# bbb.net
KiCad netlist of a schematic drawn in Altium Designer
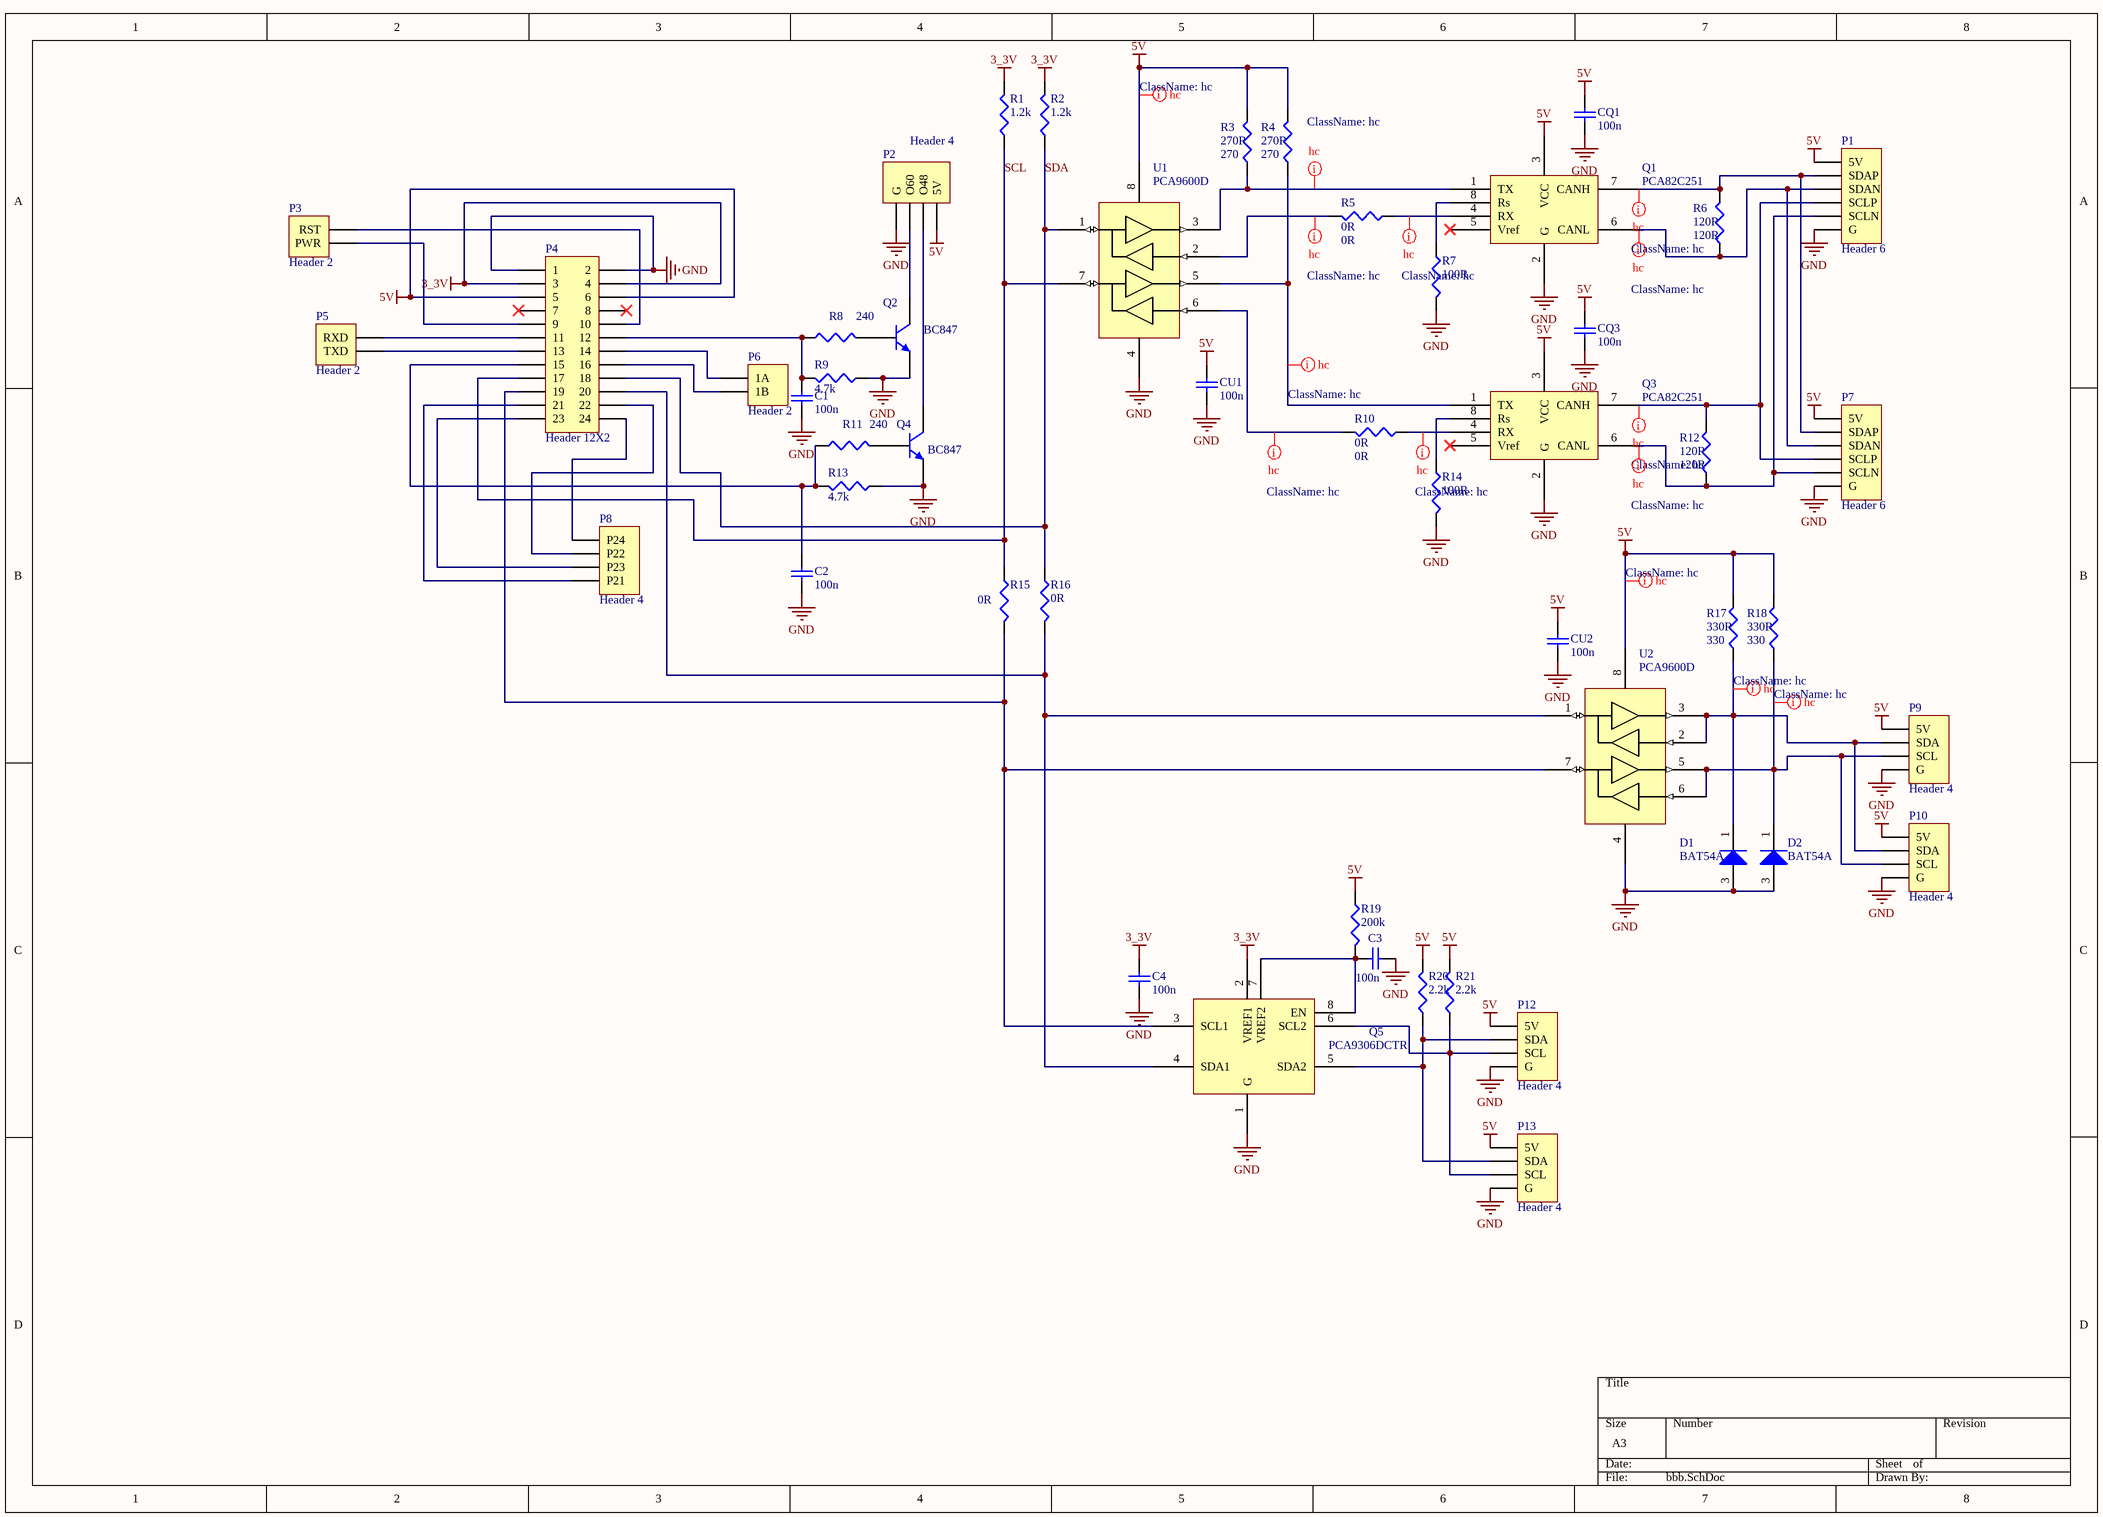
[diagram p0: bbb.SchDoc]

(export (version "E")
  (design (tool "Eeschema 10.0.6"))
  (components
    (comp (ref "C1")
      (value "100n")
      (footprint "1608[0603]")
      (description "Capacitor (Semiconductor SIM Model)")
      (fields (field (name "PUBLISHER") "Altium Limited"))
      (libsource (lib "Miscellaneous Devices") (part "Cap Semi"))
    )
    (comp (ref "C2")
      (value "100n")
      (footprint "1608[0603]")
      (description "Capacitor (Semiconductor SIM Model)")
      (fields (field (name "PUBLISHER") "Altium Limited"))
      (libsource (lib "Miscellaneous Devices") (part "Cap Semi"))
    )
    (comp (ref "C3")
      (value "100n")
      (footprint "C1206")
      (description "Capacitor (Semiconductor SIM Model)")
      (fields (field (name "PUBLISHER") "Altium Limited"))
      (libsource (lib "Miscellaneous Devices") (part "Cap Semi"))
    )
    (comp (ref "C4")
      (value "100n")
      (footprint "C1206")
      (description "Capacitor (Semiconductor SIM Model)")
      (fields (field (name "PUBLISHER") "Altium Limited"))
      (libsource (lib "Miscellaneous Devices") (part "Cap Semi"))
    )
    (comp (ref "CQ1")
      (value "100n")
      (footprint "C1206")
      (description "Capacitor (Semiconductor SIM Model)")
      (fields (field (name "PUBLISHER") "Altium Limited"))
      (libsource (lib "Miscellaneous Devices") (part "Cap Semi"))
    )
    (comp (ref "CQ3")
      (value "100n")
      (footprint "C1206")
      (description "Capacitor (Semiconductor SIM Model)")
      (fields (field (name "PUBLISHER") "Altium Limited"))
      (libsource (lib "Miscellaneous Devices") (part "Cap Semi"))
    )
    (comp (ref "CU1")
      (value "100n")
      (footprint "C1206")
      (description "Capacitor (Semiconductor SIM Model)")
      (fields (field (name "PUBLISHER") "Altium Limited"))
      (libsource (lib "Miscellaneous Devices") (part "Cap Semi"))
    )
    (comp (ref "CU2")
      (value "100n")
      (footprint "C1206")
      (description "Capacitor (Semiconductor SIM Model)")
      (fields (field (name "PUBLISHER") "Altium Limited"))
      (libsource (lib "Miscellaneous Devices") (part "Cap Semi"))
    )
    (comp (ref "D1")
      (value "BAT54A")
      (footprint "SOT-23_N")
      (description "Default Diode")
      (fields (field (name "PUBLISHER") "Altium Limited"))
      (libsource (lib "Miscellaneous Devices") (part "Diode"))
    )
    (comp (ref "D2")
      (value "BAT54A")
      (footprint "SOT-23_N")
      (description "Default Diode")
      (fields (field (name "PUBLISHER") "Altium Limited"))
      (libsource (lib "Miscellaneous Devices") (part "Diode"))
    )
    (comp (ref "P1")
      (value "Header 6")
      (footprint "HDR1X6")
      (description "Header, 6-Pin")
      (fields (field (name "PUBLISHER") "Altium Limited"))
      (libsource (lib "Miscellaneous Connectors") (part "Header 6"))
    )
    (comp (ref "P2")
      (value "Header 4")
      (footprint "HDR1X4")
      (description "Header, 4-Pin")
      (fields (field (name "PUBLISHER") "Altium Limited"))
      (libsource (lib "Miscellaneous Connectors") (part "Header 4"))
    )
    (comp (ref "P3")
      (value "Header 2")
      (footprint "HDR1X2")
      (description "Header, 2-Pin")
      (fields (field (name "PUBLISHER") "Altium Limited"))
      (libsource (lib "Miscellaneous Connectors") (part "Header 2"))
    )
    (comp (ref "P4")
      (value "Header 12X2")
      (footprint "HDR2X12")
      (description "Header, 12-Pin, Dual row")
      (fields (field (name "PUBLISHER") "Altium Limited"))
      (libsource (lib "Miscellaneous Connectors") (part "Header 12X2"))
    )
    (comp (ref "P5")
      (value "Header 2")
      (footprint "HDR1X2")
      (description "Header, 2-Pin")
      (fields (field (name "PUBLISHER") "Altium Limited"))
      (libsource (lib "Miscellaneous Connectors") (part "Header 2"))
    )
    (comp (ref "P6")
      (value "Header 2")
      (footprint "HDR1X2")
      (description "Header, 2-Pin")
      (fields (field (name "PUBLISHER") "Altium Limited"))
      (libsource (lib "") (part "Header 2_1"))
    )
    (comp (ref "P7")
      (value "Header 6")
      (footprint "HDR1X6")
      (description "Header, 6-Pin")
      (fields (field (name "PUBLISHER") "Altium Limited"))
      (libsource (lib "Miscellaneous Connectors") (part "Header 6"))
    )
    (comp (ref "P8")
      (value "Header 4")
      (footprint "HDR1X4")
      (description "Header, 4-Pin")
      (fields (field (name "PUBLISHER") "Altium Limited"))
      (libsource (lib "Miscellaneous Connectors") (part "Header 4"))
    )
    (comp (ref "P9")
      (value "Header 4")
      (footprint "HDR1X4")
      (description "Header, 4-Pin")
      (fields (field (name "PUBLISHER") "Altium Limited"))
      (libsource (lib "Miscellaneous Connectors") (part "Header 4"))
    )
    (comp (ref "P10")
      (value "Header 4")
      (footprint "HDR1X4")
      (description "Header, 4-Pin")
      (fields (field (name "PUBLISHER") "Altium Limited"))
      (libsource (lib "Miscellaneous Connectors") (part "Header 4"))
    )
    (comp (ref "P12")
      (value "Header 4")
      (footprint "HDR1X4")
      (description "Header, 4-Pin")
      (fields (field (name "PUBLISHER") "Altium Limited"))
      (libsource (lib "Miscellaneous Connectors") (part "Header 4"))
    )
    (comp (ref "P13")
      (value "Header 4")
      (footprint "HDR1X4")
      (description "Header, 4-Pin")
      (fields (field (name "PUBLISHER") "Altium Limited"))
      (libsource (lib "Miscellaneous Connectors") (part "Header 4"))
    )
    (comp (ref "Q1") (value "PCA82C251") (footprint "SOIC150-8_M") (libsource (lib "PCA") (part "PCA82C251")))
    (comp (ref "Q2")
      (value "BC847")
      (footprint "SOT-23B_N")
      (description "NPN Bipolar Transistor")
      (fields (field (name "PUBLISHER") "Altium Limited"))
      (libsource (lib "Miscellaneous Devices") (part "QNPN"))
    )
    (comp (ref "Q3") (value "PCA82C251") (footprint "SOIC150-8_M") (libsource (lib "PCA") (part "PCA82C251")))
    (comp (ref "Q4")
      (value "BC847")
      (footprint "SOT-23B_N")
      (description "NPN Bipolar Transistor")
      (fields (field (name "PUBLISHER") "Altium Limited"))
      (libsource (lib "Miscellaneous Devices") (part "QNPN"))
    )
    (comp (ref "Q5")
      (value "PCA9306DCTR")
      (footprint "DCT")
      (description "PCA9306")
      (libsource (lib "PCA") (part "PCA9306"))
    )
    (comp (ref "R1")
      (value "1.2k")
      (footprint "J1-0603")
      (description "Resistor")
      (fields (field (name "PUBLISHER") "Altium Limited"))
      (libsource (lib "Miscellaneous Devices") (part "Res3"))
    )
    (comp (ref "R2")
      (value "1.2k")
      (footprint "J1-0603")
      (description "Resistor")
      (fields (field (name "PUBLISHER") "Altium Limited"))
      (libsource (lib "Miscellaneous Devices") (part "Res3"))
    )
    (comp (ref "R3")
      (value "270R")
      (footprint "R1206")
      (description "Resistor")
      (fields (field (name "ALTIUM_VALUE") "270") (field (name "PUBLISHER") "Altium Limited"))
      (libsource (lib "Miscellaneous Devices") (part "Res3"))
    )
    (comp (ref "R4")
      (value "270R")
      (footprint "R1206")
      (description "Resistor")
      (fields (field (name "ALTIUM_VALUE") "270") (field (name "PUBLISHER") "Altium Limited"))
      (libsource (lib "Miscellaneous Devices") (part "Res3"))
    )
    (comp (ref "R5")
      (value "0R")
      (footprint "R1206")
      (description "Resistor")
      (fields (field (name "ALTIUM_VALUE") "0R") (field (name "PUBLISHER") "Altium Limited"))
      (libsource (lib "Miscellaneous Devices") (part "Res3"))
    )
    (comp (ref "R6")
      (value "120R")
      (footprint "R1206")
      (description "Resistor")
      (fields (field (name "ALTIUM_VALUE") "120R") (field (name "PUBLISHER") "Altium Limited"))
      (libsource (lib "Miscellaneous Devices") (part "Res3"))
    )
    (comp (ref "R7")
      (value "100R")
      (footprint "J1-0603")
      (description "Resistor")
      (fields (field (name "PUBLISHER") "Altium Limited"))
      (libsource (lib "Miscellaneous Devices") (part "Res3"))
    )
    (comp (ref "R8")
      (value "240")
      (footprint "J1-0603")
      (description "Resistor")
      (fields (field (name "Comment") "240R") (field (name "PUBLISHER") "Altium Limited"))
      (libsource (lib "Miscellaneous Devices") (part "Res3"))
    )
    (comp (ref "R9")
      (value "4.7k")
      (footprint "J1-0603")
      (description "Resistor")
      (fields (field (name "PUBLISHER") "Altium Limited"))
      (libsource (lib "Miscellaneous Devices") (part "Res3"))
    )
    (comp (ref "R10")
      (value "0R")
      (footprint "R1206")
      (description "Resistor")
      (fields (field (name "ALTIUM_VALUE") "0R") (field (name "PUBLISHER") "Altium Limited"))
      (libsource (lib "Miscellaneous Devices") (part "Res3"))
    )
    (comp (ref "R11")
      (value "240")
      (footprint "J1-0603")
      (description "Resistor")
      (fields (field (name "Comment") "240R") (field (name "PUBLISHER") "Altium Limited"))
      (libsource (lib "Miscellaneous Devices") (part "Res3"))
    )
    (comp (ref "R12")
      (value "120R")
      (footprint "R1206")
      (description "Resistor")
      (fields (field (name "ALTIUM_VALUE") "120R") (field (name "PUBLISHER") "Altium Limited"))
      (libsource (lib "Miscellaneous Devices") (part "Res3"))
    )
    (comp (ref "R13")
      (value "4.7k")
      (footprint "J1-0603")
      (description "Resistor")
      (fields (field (name "PUBLISHER") "Altium Limited"))
      (libsource (lib "Miscellaneous Devices") (part "Res3"))
    )
    (comp (ref "R14")
      (value "100R")
      (footprint "J1-0603")
      (description "Resistor")
      (fields (field (name "PUBLISHER") "Altium Limited"))
      (libsource (lib "Miscellaneous Devices") (part "Res3"))
    )
    (comp (ref "R15")
      (value "0R")
      (footprint "J1-0603")
      (description "Resistor")
      (fields (field (name "PUBLISHER") "Altium Limited"))
      (libsource (lib "Miscellaneous Devices") (part "Res3"))
    )
    (comp (ref "R16")
      (value "0R")
      (footprint "J1-0603")
      (description "Resistor")
      (fields (field (name "PUBLISHER") "Altium Limited"))
      (libsource (lib "Miscellaneous Devices") (part "Res3"))
    )
    (comp (ref "R17")
      (value "330R")
      (footprint "R1206")
      (description "Resistor")
      (fields (field (name "ALTIUM_VALUE") "330") (field (name "PUBLISHER") "Altium Limited"))
      (libsource (lib "Miscellaneous Devices") (part "Res3"))
    )
    (comp (ref "R18")
      (value "330R")
      (footprint "R1206")
      (description "Resistor")
      (fields (field (name "ALTIUM_VALUE") "330") (field (name "PUBLISHER") "Altium Limited"))
      (libsource (lib "Miscellaneous Devices") (part "Res3"))
    )
    (comp (ref "R19")
      (value "200k")
      (footprint "J1-0603")
      (description "Resistor")
      (fields (field (name "PUBLISHER") "Altium Limited"))
      (libsource (lib "Miscellaneous Devices") (part "Res3"))
    )
    (comp (ref "R20")
      (value "2.2k")
      (footprint "J1-0603")
      (description "Resistor")
      (fields (field (name "PUBLISHER") "Altium Limited"))
      (libsource (lib "Miscellaneous Devices") (part "Res3"))
    )
    (comp (ref "R21")
      (value "2.2k")
      (footprint "J1-0603")
      (description "Resistor")
      (fields (field (name "PUBLISHER") "Altium Limited"))
      (libsource (lib "Miscellaneous Devices") (part "Res3"))
    )
    (comp (ref "U1") (value "PCA9600D") (footprint "SOIC150-8_M") (libsource (lib "misc") (part "P82B96")))
    (comp (ref "U2") (value "PCA9600D") (footprint "SOIC150-8_M") (libsource (lib "misc") (part "P82B96")))
  )
  (nets
    (net (code "1") (name "/SCL") (class "Default")
      (node (ref "P4") (pin "17") (pinfunction "17_17") (pintype "passive"))
      (node (ref "R1") (pin "1") (pinfunction "1_1") (pintype "passive"))
      (node (ref "R15") (pin "1") (pinfunction "1_1") (pintype "passive"))
      (node (ref "U1") (pin "7") (pinfunction "7_7") (pintype "bidirectional"))
    )
    (net (code "2") (name "/SDA") (class "Default")
      (node (ref "P4") (pin "18") (pinfunction "18_18") (pintype "passive"))
      (node (ref "R16") (pin "1") (pinfunction "1_1") (pintype "passive"))
      (node (ref "R2") (pin "1") (pinfunction "1_1") (pintype "passive"))
      (node (ref "U1") (pin "1") (pinfunction "1_1") (pintype "bidirectional"))
    )
    (net (code "3") (name "3_3V") (class "Default")
      (node (ref "C4") (pin "2") (pinfunction "2_2") (pintype "passive"))
      (node (ref "P4") (pin "3") (pinfunction "3_3") (pintype "passive"))
      (node (ref "P4") (pin "4") (pinfunction "4_4") (pintype "passive"))
      (node (ref "Q5") (pin "2") (pinfunction "VREF1_2") (pintype "passive"))
      (node (ref "R1") (pin "2") (pinfunction "2_2") (pintype "passive"))
      (node (ref "R2") (pin "2") (pinfunction "2_2") (pintype "passive"))
    )
    (net (code "4") (name "5V") (class "Default")
      (node (ref "CQ1") (pin "2") (pinfunction "2_2") (pintype "passive"))
      (node (ref "CQ3") (pin "2") (pinfunction "2_2") (pintype "passive"))
      (node (ref "CU1") (pin "2") (pinfunction "2_2") (pintype "passive"))
      (node (ref "CU2") (pin "2") (pinfunction "2_2") (pintype "passive"))
      (node (ref "P1") (pin "6") (pinfunction "5V_6") (pintype "passive"))
      (node (ref "P10") (pin "4") (pinfunction "P24_4") (pintype "passive"))
      (node (ref "P12") (pin "4") (pinfunction "P24_4") (pintype "passive"))
      (node (ref "P13") (pin "4") (pinfunction "P24_4") (pintype "passive"))
      (node (ref "P2") (pin "4") (pinfunction "P24_4") (pintype "passive"))
      (node (ref "P4") (pin "5") (pinfunction "5_5") (pintype "passive"))
      (node (ref "P4") (pin "6") (pinfunction "6_6") (pintype "passive"))
      (node (ref "P7") (pin "6") (pinfunction "5V_6") (pintype "passive"))
      (node (ref "P9") (pin "4") (pinfunction "P24_4") (pintype "passive"))
      (node (ref "Q1") (pin "3") (pinfunction "VCC_3") (pintype "passive"))
      (node (ref "Q3") (pin "3") (pinfunction "VCC_3") (pintype "passive"))
      (node (ref "R17") (pin "2") (pinfunction "2_2") (pintype "passive"))
      (node (ref "R18") (pin "2") (pinfunction "2_2") (pintype "passive"))
      (node (ref "R19") (pin "1") (pinfunction "1_1") (pintype "passive"))
      (node (ref "R20") (pin "2") (pinfunction "2_2") (pintype "passive"))
      (node (ref "R21") (pin "2") (pinfunction "2_2") (pintype "passive"))
      (node (ref "R3") (pin "2") (pinfunction "2_2") (pintype "passive"))
      (node (ref "R4") (pin "2") (pinfunction "2_2") (pintype "passive"))
      (node (ref "U1") (pin "8") (pinfunction "8_8") (pintype "passive"))
      (node (ref "U2") (pin "8") (pinfunction "8_8") (pintype "passive"))
    )
    (net (code "5") (name "GND") (class "Default")
      (node (ref "C1") (pin "2") (pinfunction "2_2") (pintype "passive"))
      (node (ref "C2") (pin "2") (pinfunction "2_2") (pintype "passive"))
      (node (ref "C3") (pin "2") (pinfunction "2_2") (pintype "passive"))
      (node (ref "C4") (pin "1") (pinfunction "1_1") (pintype "passive"))
      (node (ref "CQ1") (pin "1") (pinfunction "1_1") (pintype "passive"))
      (node (ref "CQ3") (pin "1") (pinfunction "1_1") (pintype "passive"))
      (node (ref "CU1") (pin "1") (pinfunction "1_1") (pintype "passive"))
      (node (ref "CU2") (pin "1") (pinfunction "1_1") (pintype "passive"))
      (node (ref "D1") (pin "3") (pinfunction "A_3") (pintype "passive"))
      (node (ref "D2") (pin "3") (pinfunction "A_3") (pintype "passive"))
      (node (ref "P1") (pin "1") (pinfunction "G_1") (pintype "passive"))
      (node (ref "P10") (pin "1") (pinfunction "P21_1") (pintype "passive"))
      (node (ref "P12") (pin "1") (pinfunction "P21_1") (pintype "passive"))
      (node (ref "P13") (pin "1") (pinfunction "P21_1") (pintype "passive"))
      (node (ref "P2") (pin "1") (pinfunction "P21_1") (pintype "passive"))
      (node (ref "P4") (pin "1") (pinfunction "1_1") (pintype "passive"))
      (node (ref "P4") (pin "2") (pinfunction "2_2") (pintype "passive"))
      (node (ref "P7") (pin "1") (pinfunction "G_1") (pintype "passive"))
      (node (ref "P9") (pin "1") (pinfunction "P21_1") (pintype "passive"))
      (node (ref "Q1") (pin "2") (pinfunction "G_2") (pintype "passive"))
      (node (ref "Q2") (pin "3") (pinfunction "E_3") (pintype "passive"))
      (node (ref "Q3") (pin "2") (pinfunction "G_2") (pintype "passive"))
      (node (ref "Q4") (pin "3") (pinfunction "E_3") (pintype "passive"))
      (node (ref "Q5") (pin "1") (pinfunction "G_1") (pintype "passive"))
      (node (ref "R13") (pin "1") (pinfunction "1_1") (pintype "passive"))
      (node (ref "R14") (pin "2") (pinfunction "2_2") (pintype "passive"))
      (node (ref "R7") (pin "2") (pinfunction "2_2") (pintype "passive"))
      (node (ref "R9") (pin "1") (pinfunction "1_1") (pintype "passive"))
      (node (ref "U1") (pin "4") (pinfunction "4_4") (pintype "passive"))
      (node (ref "U2") (pin "4") (pinfunction "4_4") (pintype "passive"))
    )
    (net (code "6") (name "Net-(C1-Pad1)") (class "Default")
      (node (ref "C1") (pin "1") (pinfunction "1_1") (pintype "passive"))
      (node (ref "P4") (pin "12") (pinfunction "12_12") (pintype "passive"))
      (node (ref "R8") (pin "1") (pinfunction "1_1") (pintype "passive"))
      (node (ref "R9") (pin "2") (pinfunction "2_2") (pintype "passive"))
    )
    (net (code "7") (name "Net-(C2-Pad1)") (class "Default")
      (node (ref "C2") (pin "1") (pinfunction "1_1") (pintype "passive"))
      (node (ref "P4") (pin "15") (pinfunction "15_15") (pintype "passive"))
      (node (ref "R11") (pin "1") (pinfunction "1_1") (pintype "passive"))
      (node (ref "R13") (pin "2") (pinfunction "2_2") (pintype "passive"))
    )
    (net (code "8") (name "Net-(D1-K)") (class "Default")
      (node (ref "D1") (pin "1") (pinfunction "K_1") (pintype "passive"))
      (node (ref "P10") (pin "3") (pinfunction "P22_3") (pintype "passive"))
      (node (ref "P9") (pin "3") (pinfunction "P22_3") (pintype "passive"))
      (node (ref "R17") (pin "1") (pinfunction "1_1") (pintype "passive"))
      (node (ref "U2") (pin "2") (pinfunction "2_2") (pintype "input"))
      (node (ref "U2") (pin "3") (pinfunction "3_3") (pintype "output"))
    )
    (net (code "9") (name "Net-(D2-K)") (class "Default")
      (node (ref "D2") (pin "1") (pinfunction "K_1") (pintype "passive"))
      (node (ref "P10") (pin "2") (pinfunction "P23_2") (pintype "passive"))
      (node (ref "P9") (pin "2") (pinfunction "P23_2") (pintype "passive"))
      (node (ref "R18") (pin "1") (pinfunction "1_1") (pintype "passive"))
      (node (ref "U2") (pin "5") (pinfunction "5_5") (pintype "output"))
      (node (ref "U2") (pin "6") (pinfunction "6_6") (pintype "input"))
    )
    (net (code "10") (name "Net-(P1-SCLN)") (class "Default")
      (node (ref "P1") (pin "2") (pinfunction "SCLN_2") (pintype "passive"))
      (node (ref "P7") (pin "2") (pinfunction "SCLN_2") (pintype "passive"))
      (node (ref "Q3") (pin "6") (pinfunction "CANL_6") (pintype "passive"))
      (node (ref "R12") (pin "1") (pinfunction "1_1") (pintype "passive"))
    )
    (net (code "11") (name "Net-(P1-SCLP)") (class "Default")
      (node (ref "P1") (pin "3") (pinfunction "SCLP_3") (pintype "passive"))
      (node (ref "P7") (pin "3") (pinfunction "SCLP_3") (pintype "passive"))
      (node (ref "Q3") (pin "7") (pinfunction "CANH_7") (pintype "passive"))
      (node (ref "R12") (pin "2") (pinfunction "2_2") (pintype "passive"))
    )
    (net (code "12") (name "Net-(P1-SDAN)") (class "Default")
      (node (ref "P1") (pin "4") (pinfunction "SDAN_4") (pintype "passive"))
      (node (ref "P7") (pin "4") (pinfunction "SDAN_4") (pintype "passive"))
      (node (ref "Q1") (pin "6") (pinfunction "CANL_6") (pintype "passive"))
      (node (ref "R6") (pin "1") (pinfunction "1_1") (pintype "passive"))
    )
    (net (code "13") (name "Net-(P1-SDAP)") (class "Default")
      (node (ref "P1") (pin "5") (pinfunction "SDAP_5") (pintype "passive"))
      (node (ref "P7") (pin "5") (pinfunction "SDAP_5") (pintype "passive"))
      (node (ref "Q1") (pin "7") (pinfunction "CANH_7") (pintype "passive"))
      (node (ref "R6") (pin "2") (pinfunction "2_2") (pintype "passive"))
    )
    (net (code "14") (name "Net-(P2-P22)") (class "Default")
      (node (ref "P2") (pin "3") (pinfunction "P22_3") (pintype "passive"))
      (node (ref "Q4") (pin "1") (pinfunction "C_1") (pintype "passive"))
    )
    (net (code "15") (name "Net-(P2-P23)") (class "Default")
      (node (ref "P2") (pin "2") (pinfunction "P23_2") (pintype "passive"))
      (node (ref "Q2") (pin "1") (pinfunction "C_1") (pintype "passive"))
    )
    (net (code "16") (name "Net-(P3-PWR)") (class "Default")
      (node (ref "P3") (pin "1") (pinfunction "PWR_1") (pintype "passive"))
      (node (ref "P4") (pin "9") (pinfunction "9_9") (pintype "passive"))
    )
    (net (code "17") (name "Net-(P3-RST)") (class "Default")
      (node (ref "P3") (pin "2") (pinfunction "RST_2") (pintype "passive"))
      (node (ref "P4") (pin "10") (pinfunction "10_10") (pintype "passive"))
    )
    (net (code "18") (name "Net-(P5-PWR)") (class "Default")
      (node (ref "P4") (pin "13") (pinfunction "13_13") (pintype "passive"))
      (node (ref "P5") (pin "1") (pinfunction "PWR_1") (pintype "passive"))
    )
    (net (code "19") (name "Net-(P5-RST)") (class "Default")
      (node (ref "P4") (pin "11") (pinfunction "11_11") (pintype "passive"))
      (node (ref "P5") (pin "2") (pinfunction "RST_2") (pintype "passive"))
    )
    (net (code "20") (name "Net-(P6-1A)") (class "Default")
      (node (ref "P4") (pin "14") (pinfunction "14_14") (pintype "passive"))
      (node (ref "P6") (pin "1") (pinfunction "1A_1") (pintype "passive"))
    )
    (net (code "21") (name "Net-(P6-1B)") (class "Default")
      (node (ref "P4") (pin "16") (pinfunction "16_16") (pintype "passive"))
      (node (ref "P6") (pin "2") (pinfunction "1B_2") (pintype "passive"))
    )
    (net (code "22") (name "Net-(P8-P21)") (class "Default")
      (node (ref "P4") (pin "21") (pinfunction "21_21") (pintype "passive"))
      (node (ref "P8") (pin "1") (pinfunction "P21_1") (pintype "passive"))
    )
    (net (code "23") (name "Net-(P8-P22)") (class "Default")
      (node (ref "P4") (pin "22") (pinfunction "22_22") (pintype "passive"))
      (node (ref "P8") (pin "3") (pinfunction "P22_3") (pintype "passive"))
    )
    (net (code "24") (name "Net-(P8-P23)") (class "Default")
      (node (ref "P4") (pin "23") (pinfunction "23_23") (pintype "passive"))
      (node (ref "P8") (pin "2") (pinfunction "P23_2") (pintype "passive"))
    )
    (net (code "25") (name "Net-(P8-P24)") (class "Default")
      (node (ref "P4") (pin "24") (pinfunction "24_24") (pintype "passive"))
      (node (ref "P8") (pin "4") (pinfunction "P24_4") (pintype "passive"))
    )
    (net (code "26") (name "Net-(P12-P22)") (class "Default")
      (node (ref "P12") (pin "3") (pinfunction "P22_3") (pintype "passive"))
      (node (ref "P13") (pin "3") (pinfunction "P22_3") (pintype "passive"))
      (node (ref "Q5") (pin "5") (pinfunction "SDA2_5") (pintype "passive"))
      (node (ref "R20") (pin "1") (pinfunction "1_1") (pintype "passive"))
    )
    (net (code "27") (name "Net-(P12-P23)") (class "Default")
      (node (ref "P12") (pin "2") (pinfunction "P23_2") (pintype "passive"))
      (node (ref "P13") (pin "2") (pinfunction "P23_2") (pintype "passive"))
      (node (ref "Q5") (pin "6") (pinfunction "SCL2_6") (pintype "passive"))
      (node (ref "R21") (pin "1") (pinfunction "1_1") (pintype "passive"))
    )
    (net (code "28") (name "Net-(Q1-RX)") (class "Default")
      (node (ref "Q1") (pin "4") (pinfunction "RX_4") (pintype "passive"))
      (node (ref "R5") (pin "1") (pinfunction "1_1") (pintype "passive"))
    )
    (net (code "29") (name "Net-(Q1-Rs)") (class "Default")
      (node (ref "Q1") (pin "8") (pinfunction "Rs_8") (pintype "passive"))
      (node (ref "R7") (pin "1") (pinfunction "1_1") (pintype "passive"))
    )
    (net (code "30") (name "Net-(Q1-TX)") (class "Default")
      (node (ref "Q1") (pin "1") (pinfunction "TX_1") (pintype "passive"))
      (node (ref "R3") (pin "1") (pinfunction "1_1") (pintype "passive"))
      (node (ref "U1") (pin "3") (pinfunction "3_3") (pintype "output"))
    )
    (net (code "31") (name "Net-(Q2-B)") (class "Default")
      (node (ref "Q2") (pin "2") (pinfunction "B_2") (pintype "passive"))
      (node (ref "R8") (pin "2") (pinfunction "2_2") (pintype "passive"))
    )
    (net (code "32") (name "Net-(Q3-RX)") (class "Default")
      (node (ref "Q3") (pin "4") (pinfunction "RX_4") (pintype "passive"))
      (node (ref "R10") (pin "1") (pinfunction "1_1") (pintype "passive"))
    )
    (net (code "33") (name "Net-(Q3-Rs)") (class "Default")
      (node (ref "Q3") (pin "8") (pinfunction "Rs_8") (pintype "passive"))
      (node (ref "R14") (pin "1") (pinfunction "1_1") (pintype "passive"))
    )
    (net (code "34") (name "Net-(Q3-TX)") (class "Default")
      (node (ref "Q3") (pin "1") (pinfunction "TX_1") (pintype "passive"))
      (node (ref "R4") (pin "1") (pinfunction "1_1") (pintype "passive"))
      (node (ref "U1") (pin "5") (pinfunction "5_5") (pintype "output"))
    )
    (net (code "35") (name "Net-(Q4-B)") (class "Default")
      (node (ref "Q4") (pin "2") (pinfunction "B_2") (pintype "passive"))
      (node (ref "R11") (pin "2") (pinfunction "2_2") (pintype "passive"))
    )
    (net (code "36") (name "Net-(Q5-EN)") (class "Default")
      (node (ref "C3") (pin "1") (pinfunction "1_1") (pintype "passive"))
      (node (ref "Q5") (pin "7") (pinfunction "VREF2_7") (pintype "passive"))
      (node (ref "Q5") (pin "8") (pinfunction "EN_8") (pintype "passive"))
      (node (ref "R19") (pin "2") (pinfunction "2_2") (pintype "passive"))
    )
    (net (code "37") (name "Net-(Q5-SCL1)") (class "Default")
      (node (ref "P4") (pin "19") (pinfunction "19_19") (pintype "passive"))
      (node (ref "Q5") (pin "3") (pinfunction "SCL1_3") (pintype "passive"))
      (node (ref "R15") (pin "2") (pinfunction "2_2") (pintype "passive"))
      (node (ref "U2") (pin "7") (pinfunction "7_7") (pintype "bidirectional"))
    )
    (net (code "38") (name "Net-(Q5-SDA1)") (class "Default")
      (node (ref "P4") (pin "20") (pinfunction "20_20") (pintype "passive"))
      (node (ref "Q5") (pin "4") (pinfunction "SDA1_4") (pintype "passive"))
      (node (ref "R16") (pin "2") (pinfunction "2_2") (pintype "passive"))
      (node (ref "U2") (pin "1") (pinfunction "1_1") (pintype "bidirectional"))
    )
    (net (code "39") (name "Net-(R5-Pad2)") (class "Default")
      (node (ref "R5") (pin "2") (pinfunction "2_2") (pintype "passive"))
      (node (ref "U1") (pin "2") (pinfunction "2_2") (pintype "input"))
    )
    (net (code "40") (name "Net-(R10-Pad2)") (class "Default")
      (node (ref "R10") (pin "2") (pinfunction "2_2") (pintype "passive"))
      (node (ref "U1") (pin "6") (pinfunction "6_6") (pintype "input"))
    )
    (net (code "41") (name "unconnected-(P4-Pad7)") (class "Default")
      (node (ref "P4") (pin "7") (pinfunction "7_7") (pintype "passive+no_connect"))
    )
    (net (code "42") (name "unconnected-(P4-Pad8)") (class "Default")
      (node (ref "P4") (pin "8") (pinfunction "8_8") (pintype "passive+no_connect"))
    )
    (net (code "43") (name "unconnected-(Q1-Vref-Pad5)") (class "Default")
      (node (ref "Q1") (pin "5") (pinfunction "Vref_5") (pintype "passive+no_connect"))
    )
    (net (code "44") (name "unconnected-(Q3-Vref-Pad5)") (class "Default")
      (node (ref "Q3") (pin "5") (pinfunction "Vref_5") (pintype "passive+no_connect"))
    )
  )
)
